# ValveDriver-8ch.net
KiCad netlist of a schematic drawn in EAGLE
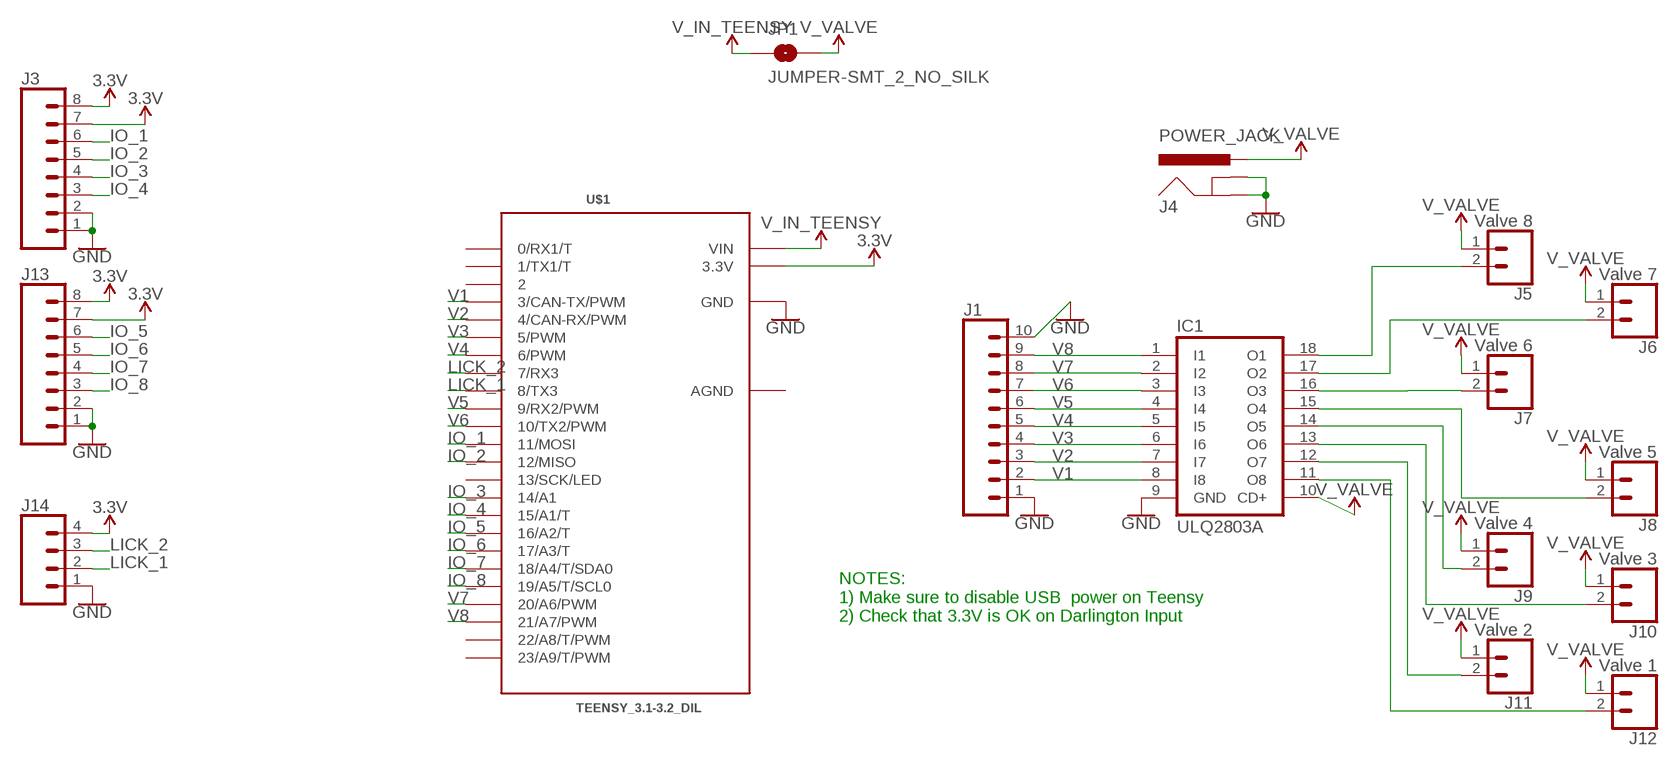
[diagram p0: schematic, sheet 1]

(export (version "E")
  (design (tool "Eeschema 10.0.6"))
  (components
    (comp (ref "IC1")
      (value "ULQ2803A")
      (footprint "eagle-import:DIL18")
      (libsource (lib "eagle-import") (part "ULN2803A"))
    )
    (comp (ref "J1")
      (value "CONN_10\"")
      (footprint "eagle-import:1X10")
      (libsource (lib "eagle-import") (part "CONN_10{dblquote}"))
    )
    (comp (ref "J3")
      (value "CONN_083.5MM-8")
      (footprint "eagle-import:SCREWTERMINAL-3.5MM-8")
      (libsource (lib "eagle-import") (part "CONN_083.5MM-8"))
    )
    (comp (ref "J4")
      (value "POWER_JACK")
      (footprint "eagle-import:POWER_JACK_PTH")
      (libsource (lib "eagle-import") (part "POWER_JACK"))
    )
    (comp (ref "J5")
      (value "Valve 8")
      (footprint "eagle-import:1X02")
      (libsource (lib "eagle-import") (part "CONN_02"))
    )
    (comp (ref "J6")
      (value "Valve 7")
      (footprint "eagle-import:1X02")
      (libsource (lib "eagle-import") (part "CONN_02"))
    )
    (comp (ref "J7")
      (value "Valve 6")
      (footprint "eagle-import:1X02")
      (libsource (lib "eagle-import") (part "CONN_02"))
    )
    (comp (ref "J8")
      (value "Valve 5")
      (footprint "eagle-import:1X02")
      (libsource (lib "eagle-import") (part "CONN_02"))
    )
    (comp (ref "J9")
      (value "Valve 4")
      (footprint "eagle-import:1X02")
      (libsource (lib "eagle-import") (part "CONN_02"))
    )
    (comp (ref "J10")
      (value "Valve 3")
      (footprint "eagle-import:1X02")
      (libsource (lib "eagle-import") (part "CONN_02"))
    )
    (comp (ref "J11")
      (value "Valve 2")
      (footprint "eagle-import:1X02")
      (libsource (lib "eagle-import") (part "CONN_02"))
    )
    (comp (ref "J12")
      (value "Valve 1")
      (footprint "eagle-import:1X02")
      (libsource (lib "eagle-import") (part "CONN_02"))
    )
    (comp (ref "J13")
      (value "CONN_083.5MM-8")
      (footprint "eagle-import:SCREWTERMINAL-3.5MM-8")
      (libsource (lib "eagle-import") (part "CONN_083.5MM-8"))
    )
    (comp (ref "J14")
      (value "CONN_04")
      (footprint "eagle-import:1X04")
      (libsource (lib "eagle-import") (part "CONN_04"))
    )
    (comp (ref "JP1")
      (value "JUMPER-SMT_2_NO_SILK")
      (footprint "eagle-import:SMT-JUMPER_2_NO_SILK")
      (libsource (lib "eagle-import") (part "JUMPER-SMT_2_NO_SILK"))
    )
    (comp (ref "U$1")
      (value "TEENSY_3.1-3.2_DIL")
      (footprint "eagle-import:TEENSY_3.0-3.2&LC_DIL")
      (libsource (lib "eagle-import") (part "TEENSY_3.1-3.2_DIL"))
    )
  )
  (nets
    (net (code "1") (name "/AGND") (class "Default")
      (node (ref "U$1") (pin "AGND") (pinfunction "AGND_AGND") (pintype "power_in"))
    )
    (net (code "2") (name "/IO_1") (class "Default")
      (node (ref "J3") (pin "6") (pinfunction "6_6") (pintype "passive"))
      (node (ref "U$1") (pin "11") (pinfunction "11/MOSI_11") (pintype "bidirectional"))
    )
    (net (code "3") (name "/IO_2") (class "Default")
      (node (ref "J3") (pin "5") (pinfunction "5_5") (pintype "passive"))
      (node (ref "U$1") (pin "12") (pinfunction "12/MISO_12") (pintype "bidirectional"))
    )
    (net (code "4") (name "/IO_3") (class "Default")
      (node (ref "J3") (pin "4") (pinfunction "4_4") (pintype "passive"))
      (node (ref "U$1") (pin "14/A0") (pinfunction "14/A1_14/A0") (pintype "bidirectional"))
    )
    (net (code "5") (name "/IO_4") (class "Default")
      (node (ref "J3") (pin "3") (pinfunction "3_3") (pintype "passive"))
      (node (ref "U$1") (pin "15/A1") (pinfunction "15/A1/T_15/A1") (pintype "bidirectional"))
    )
    (net (code "6") (name "/IO_5") (class "Default")
      (node (ref "J13") (pin "6") (pinfunction "6_6") (pintype "passive"))
      (node (ref "U$1") (pin "16/A2") (pinfunction "16/A2/T_16/A2") (pintype "bidirectional"))
    )
    (net (code "7") (name "/IO_6") (class "Default")
      (node (ref "J13") (pin "5") (pinfunction "5_5") (pintype "passive"))
      (node (ref "U$1") (pin "17/A3") (pinfunction "17/A3/T_17/A3") (pintype "bidirectional"))
    )
    (net (code "8") (name "/IO_7") (class "Default")
      (node (ref "J13") (pin "4") (pinfunction "4_4") (pintype "passive"))
      (node (ref "U$1") (pin "18/A4") (pinfunction "18/A4/T/SDA0_18/A4") (pintype "bidirectional"))
    )
    (net (code "9") (name "/IO_8") (class "Default")
      (node (ref "J13") (pin "3") (pinfunction "3_3") (pintype "passive"))
      (node (ref "U$1") (pin "19/A5") (pinfunction "19/A5/T/SCL0_19/A5") (pintype "bidirectional"))
    )
    (net (code "10") (name "/LICK_1") (class "Default")
      (node (ref "J14") (pin "2") (pinfunction "2_2") (pintype "passive"))
      (node (ref "U$1") (pin "8") (pinfunction "8/TX3_8") (pintype "bidirectional"))
    )
    (net (code "11") (name "/LICK_2") (class "Default")
      (node (ref "J14") (pin "3") (pinfunction "3_3") (pintype "passive"))
      (node (ref "U$1") (pin "7") (pinfunction "7/RX3_7") (pintype "bidirectional"))
    )
    (net (code "12") (name "/V1") (class "Default")
      (node (ref "IC1") (pin "8") (pinfunction "I8_8") (pintype "input"))
      (node (ref "J1") (pin "2") (pinfunction "2_2") (pintype "passive"))
      (node (ref "U$1") (pin "3") (pinfunction "3/CAN-TX/PWM_3") (pintype "bidirectional"))
    )
    (net (code "13") (name "/V2") (class "Default")
      (node (ref "IC1") (pin "7") (pinfunction "I7_7") (pintype "input"))
      (node (ref "J1") (pin "3") (pinfunction "3_3") (pintype "passive"))
      (node (ref "U$1") (pin "4") (pinfunction "4/CAN-RX/PWM_4") (pintype "bidirectional"))
    )
    (net (code "14") (name "/V3") (class "Default")
      (node (ref "IC1") (pin "6") (pinfunction "I6_6") (pintype "input"))
      (node (ref "J1") (pin "4") (pinfunction "4_4") (pintype "passive"))
      (node (ref "U$1") (pin "5") (pinfunction "5/PWM_5") (pintype "bidirectional"))
    )
    (net (code "15") (name "/V4") (class "Default")
      (node (ref "IC1") (pin "5") (pinfunction "I5_5") (pintype "input"))
      (node (ref "J1") (pin "5") (pinfunction "5_5") (pintype "passive"))
      (node (ref "U$1") (pin "6") (pinfunction "6/PWM_6") (pintype "bidirectional"))
    )
    (net (code "16") (name "/V5") (class "Default")
      (node (ref "IC1") (pin "4") (pinfunction "I4_4") (pintype "input"))
      (node (ref "J1") (pin "6") (pinfunction "6_6") (pintype "passive"))
      (node (ref "U$1") (pin "9") (pinfunction "9/RX2/PWM_9") (pintype "bidirectional"))
    )
    (net (code "17") (name "/V6") (class "Default")
      (node (ref "IC1") (pin "3") (pinfunction "I3_3") (pintype "input"))
      (node (ref "J1") (pin "7") (pinfunction "7_7") (pintype "passive"))
      (node (ref "U$1") (pin "10") (pinfunction "10/TX2/PWM_10") (pintype "bidirectional"))
    )
    (net (code "18") (name "/V7") (class "Default")
      (node (ref "IC1") (pin "2") (pinfunction "I2_2") (pintype "input"))
      (node (ref "J1") (pin "8") (pinfunction "8_8") (pintype "passive"))
      (node (ref "U$1") (pin "20/A6") (pinfunction "20/A6/PWM_20/A6") (pintype "bidirectional"))
    )
    (net (code "19") (name "/V8") (class "Default")
      (node (ref "IC1") (pin "1") (pinfunction "I1_1") (pintype "input"))
      (node (ref "J1") (pin "9") (pinfunction "9_9") (pintype "passive"))
      (node (ref "U$1") (pin "21/A7") (pinfunction "21/A7/PWM_21/A7") (pintype "bidirectional"))
    )
    (net (code "20") (name "3.3V") (class "Default")
      (node (ref "J13") (pin "7") (pinfunction "7_7") (pintype "passive"))
      (node (ref "J13") (pin "8") (pinfunction "8_8") (pintype "passive"))
      (node (ref "J14") (pin "4") (pinfunction "4_4") (pintype "passive"))
      (node (ref "J3") (pin "7") (pinfunction "7_7") (pintype "passive"))
      (node (ref "J3") (pin "8") (pinfunction "8_8") (pintype "passive"))
      (node (ref "U$1") (pin "3.3V") (pinfunction "3.3V_3.3V") (pintype "power_in"))
    )
    (net (code "21") (name "GND") (class "Default")
      (node (ref "IC1") (pin "9") (pinfunction "GND_9") (pintype "power_in"))
      (node (ref "J1") (pin "1") (pinfunction "1_1") (pintype "passive"))
      (node (ref "J1") (pin "10") (pinfunction "10_10") (pintype "passive"))
      (node (ref "J13") (pin "1") (pinfunction "1_1") (pintype "passive"))
      (node (ref "J13") (pin "2") (pinfunction "2_2") (pintype "passive"))
      (node (ref "J14") (pin "1") (pinfunction "1_1") (pintype "passive"))
      (node (ref "J3") (pin "1") (pinfunction "1_1") (pintype "passive"))
      (node (ref "J3") (pin "2") (pinfunction "2_2") (pintype "passive"))
      (node (ref "J4") (pin "GND") (pinfunction "GND_GND") (pintype "bidirectional"))
      (node (ref "J4") (pin "GNDBREAK") (pinfunction "GNDBREAK_GNDBREAK") (pintype "bidirectional"))
      (node (ref "U$1") (pin "GND") (pinfunction "GND_GND") (pintype "power_in"))
    )
    (net (code "22") (name "Net-(IC1-O1)") (class "Default")
      (node (ref "IC1") (pin "18") (pinfunction "O1_18") (pintype "open_collector"))
      (node (ref "J5") (pin "2") (pinfunction "2_2") (pintype "passive"))
    )
    (net (code "23") (name "Net-(IC1-O2)") (class "Default")
      (node (ref "IC1") (pin "17") (pinfunction "O2_17") (pintype "open_collector"))
      (node (ref "J6") (pin "2") (pinfunction "2_2") (pintype "passive"))
    )
    (net (code "24") (name "Net-(IC1-O3)") (class "Default")
      (node (ref "IC1") (pin "16") (pinfunction "O3_16") (pintype "open_collector"))
      (node (ref "J7") (pin "2") (pinfunction "2_2") (pintype "passive"))
    )
    (net (code "25") (name "Net-(IC1-O4)") (class "Default")
      (node (ref "IC1") (pin "15") (pinfunction "O4_15") (pintype "open_collector"))
      (node (ref "J8") (pin "2") (pinfunction "2_2") (pintype "passive"))
    )
    (net (code "26") (name "Net-(IC1-O5)") (class "Default")
      (node (ref "IC1") (pin "14") (pinfunction "O5_14") (pintype "open_collector"))
      (node (ref "J9") (pin "2") (pinfunction "2_2") (pintype "passive"))
    )
    (net (code "27") (name "Net-(IC1-O6)") (class "Default")
      (node (ref "IC1") (pin "13") (pinfunction "O6_13") (pintype "open_collector"))
      (node (ref "J10") (pin "2") (pinfunction "2_2") (pintype "passive"))
    )
    (net (code "28") (name "Net-(IC1-O7)") (class "Default")
      (node (ref "IC1") (pin "12") (pinfunction "O7_12") (pintype "open_collector"))
      (node (ref "J11") (pin "2") (pinfunction "2_2") (pintype "passive"))
    )
    (net (code "29") (name "Net-(IC1-O8)") (class "Default")
      (node (ref "IC1") (pin "11") (pinfunction "O8_11") (pintype "open_collector"))
      (node (ref "J12") (pin "2") (pinfunction "2_2") (pintype "passive"))
    )
    (net (code "30") (name "V_IN_TEENSY") (class "Default")
      (node (ref "JP1") (pin "1") (pinfunction "1_1") (pintype "passive"))
      (node (ref "U$1") (pin "VIN") (pinfunction "VIN_VIN") (pintype "power_in"))
    )
    (net (code "31") (name "V_VALVE") (class "Default")
      (node (ref "IC1") (pin "10") (pinfunction "CD+_10") (pintype "passive"))
      (node (ref "J10") (pin "1") (pinfunction "1_1") (pintype "passive"))
      (node (ref "J11") (pin "1") (pinfunction "1_1") (pintype "passive"))
      (node (ref "J12") (pin "1") (pinfunction "1_1") (pintype "passive"))
      (node (ref "J4") (pin "PWR") (pinfunction "PWR_PWR") (pintype "bidirectional"))
      (node (ref "J5") (pin "1") (pinfunction "1_1") (pintype "passive"))
      (node (ref "J6") (pin "1") (pinfunction "1_1") (pintype "passive"))
      (node (ref "J7") (pin "1") (pinfunction "1_1") (pintype "passive"))
      (node (ref "J8") (pin "1") (pinfunction "1_1") (pintype "passive"))
      (node (ref "J9") (pin "1") (pinfunction "1_1") (pintype "passive"))
      (node (ref "JP1") (pin "2") (pinfunction "2_2") (pintype "passive"))
    )
    (net (code "32") (name "unconnected-(U$1-0{slash}RX1{slash}T-Pad0)") (class "Default")
      (node (ref "U$1") (pin "0") (pinfunction "0/RX1/T_0") (pintype "bidirectional"))
    )
    (net (code "33") (name "unconnected-(U$1-1{slash}TX1{slash}T-Pad1)") (class "Default")
      (node (ref "U$1") (pin "1") (pinfunction "1/TX1/T_1") (pintype "bidirectional"))
    )
    (net (code "34") (name "unconnected-(U$1-13{slash}SCK{slash}LED-Pad13)") (class "Default")
      (node (ref "U$1") (pin "13") (pinfunction "13/SCK/LED_13") (pintype "bidirectional"))
    )
    (net (code "35") (name "unconnected-(U$1-22{slash}A8{slash}T{slash}PWM-Pad22{slash}A8)") (class "Default")
      (node (ref "U$1") (pin "22/A8") (pinfunction "22/A8/T/PWM_22/A8") (pintype "bidirectional"))
    )
    (net (code "36") (name "unconnected-(U$1-23{slash}A9{slash}T{slash}PWM-Pad23{slash}A9)") (class "Default")
      (node (ref "U$1") (pin "23/A9") (pinfunction "23/A9/T/PWM_23/A9") (pintype "bidirectional"))
    )
    (net (code "37") (name "unconnected-(U$1-Pad2)") (class "Default")
      (node (ref "U$1") (pin "2") (pinfunction "2_2") (pintype "bidirectional"))
    )
  )
)
